# System.net
KiCad netlist of a schematic drawn in Altium Designer
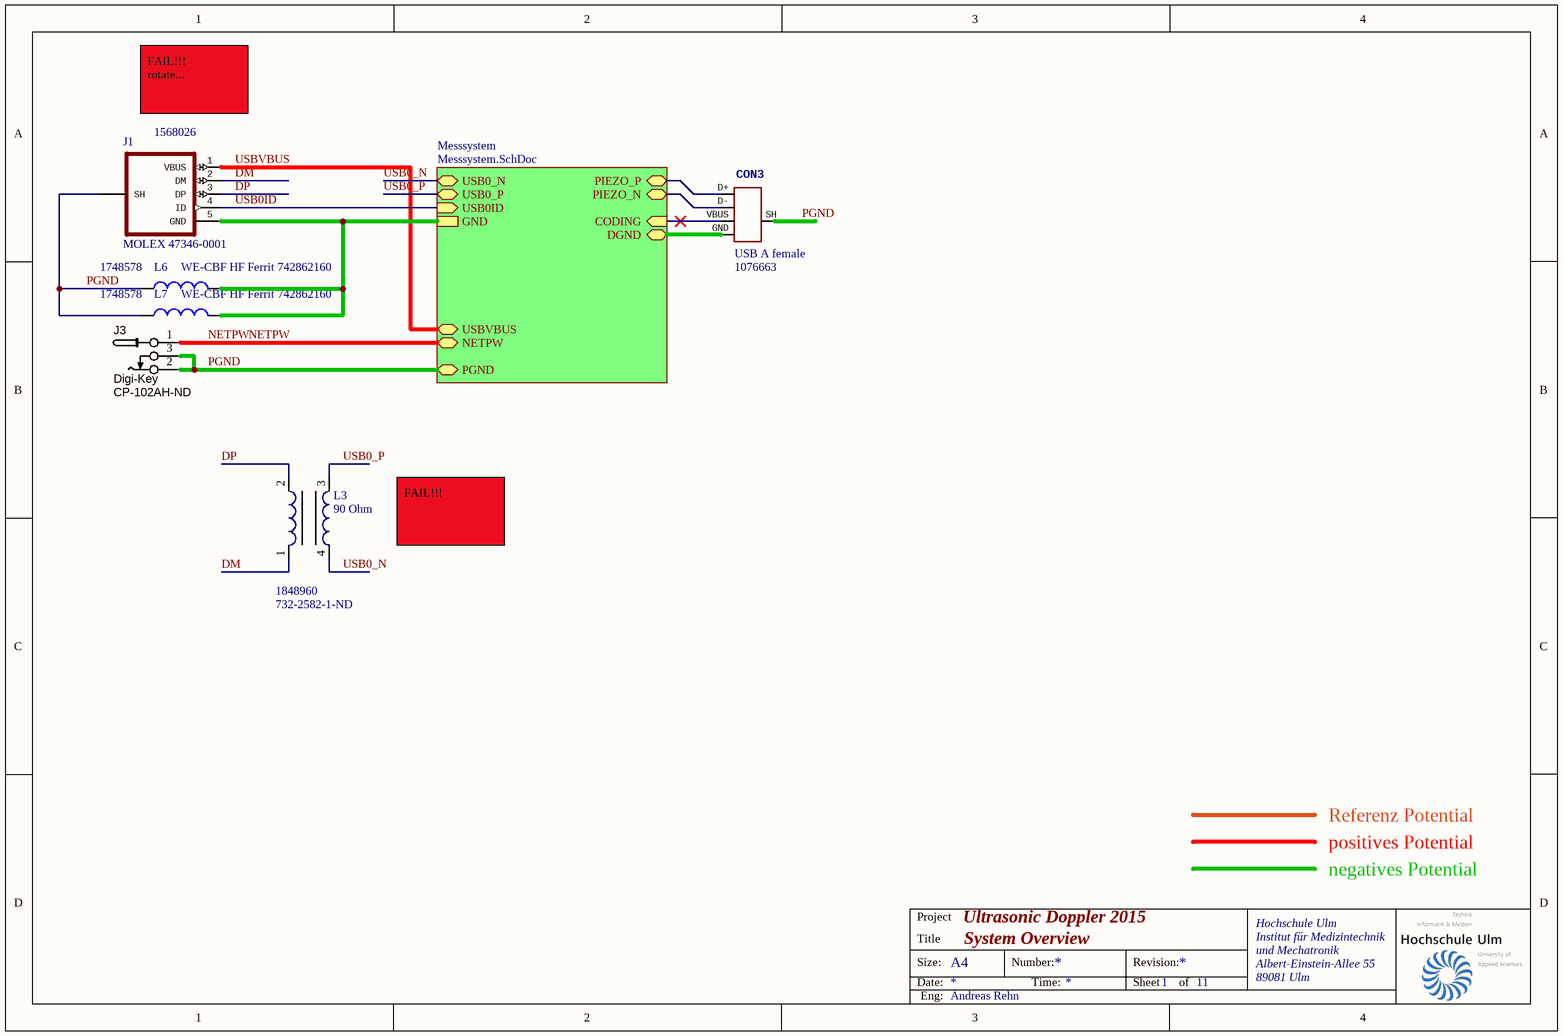
[diagram p0: System.SchDoc]

(export (version "E")
  (design (tool "Eeschema 10.0.6"))
  (components
    (comp (ref "CON3")
      (value "USB A female")
      (footprint "USB A female")
      (fields (field (name "SUPPLIER PART NUMBER 1") "1076663"))
      (libsource (lib "USD Parts") (part "USB-MB-S"))
    )
    (comp (ref "J1")
      (value "MOLEX 47346-0001")
      (footprint "USB Micro")
      (description "MICRO USB 2.0 BUCHSE, TYP B, SMD")
      (fields (field (name "SUPPLIER PART NUMBER 1") "1568026"))
      (libsource (lib "USD Parts") (part "USB"))
    )
    (comp (ref "J3")
      (value "CONN_PWR_JACK_2.1x5.5mm")
      (footprint "CONN_PWR_JACK_2.1x5.5mm")
      (description "Power Connector, THT, 2.1mm ID, 5.5mm OD")
      (fields (field (name "SUPPLIER 1") "Digi-Key") (field (name "SUPPLIER PART NUMBER 1") "CP-102AH-ND"))
      (libsource (lib "USD Parts") (part "CONN_PWR_JACK_2.1x5.5mm"))
    )
    (comp (ref "L3")
      (value "90 Ohm")
      (footprint "WE-CNSW, 0603")
      (description "SMD Common Mode Noise Suppressor WE-CNSW,  Z= 90 Ohm")
      (fields
        (field (name "PARTNO") "744230900")
        (field (name "MANUFACTURER") "Würth Elektronik eiSos GmbH")
        (field (name "SUPPLIER PART NUMBER 1") "1848960")
        (field (name "SUPPLIER PART NUMBER 2") "732-2582-1-ND")
        (field (name "CREATED BY") "Christin Zierenner")
      )
      (libsource (lib "WE-CNSW") (part "WE-CNSW 0603, 744230900"))
    )
    (comp (ref "L6")
      (value "WE-CBF HF Ferrit 742862160")
      (footprint "0603[1508]")
      (description "Ferrit")
      (fields (field (name "SUPPLIER PART NUMBER 1") "1748578") (field (name "PUBLISHER") "Altium Limited"))
      (libsource (lib "Components") (part "Inductor"))
    )
    (comp (ref "L7")
      (value "WE-CBF HF Ferrit 742862160")
      (footprint "0603[1508]")
      (description "Ferrit")
      (fields (field (name "SUPPLIER PART NUMBER 1") "1748578") (field (name "PUBLISHER") "Altium Limited"))
      (libsource (lib "Components") (part "Inductor"))
    )
  )
  (nets
    (net (code "1") (name "/CODING") (class "Default")
      (node (ref "CON3") (pin "VBUS") (pinfunction "VBUS_VBUS") (pintype "power_in"))
    )
    (net (code "2") (name "/DGND") (class "Default")
      (node (ref "CON3") (pin "GND") (pinfunction "GND_GND") (pintype "passive"))
    )
    (net (code "3") (name "/DM") (class "Default")
      (node (ref "J1") (pin "2") (pinfunction "DM_2") (pintype "bidirectional"))
      (node (ref "L3") (pin "1") (pinfunction "1_1") (pintype "passive"))
    )
    (net (code "4") (name "/DP") (class "Default")
      (node (ref "J1") (pin "3") (pinfunction "DP_3") (pintype "bidirectional"))
      (node (ref "L3") (pin "2") (pinfunction "2_2") (pintype "passive"))
    )
    (net (code "5") (name "/GND") (class "Default")
      (node (ref "J1") (pin "5") (pinfunction "GND_5") (pintype "passive"))
      (node (ref "L6") (pin "2") (pinfunction "2_2") (pintype "passive"))
      (node (ref "L7") (pin "2") (pinfunction "2_2") (pintype "passive"))
    )
    (net (code "6") (name "/NETPW") (class "Default")
      (node (ref "J3") (pin "1") (pinfunction "1_1") (pintype "passive"))
    )
    (net (code "7") (name "/PGND") (class "Default")
      (node (ref "CON3") (pin "SH") (pinfunction "SH_SH") (pintype "passive"))
      (node (ref "J1") (pin "SH") (pinfunction "SH_SH") (pintype "passive"))
      (node (ref "J3") (pin "2") (pinfunction "2_2") (pintype "passive"))
      (node (ref "J3") (pin "3") (pinfunction "3_3") (pintype "passive"))
      (node (ref "L6") (pin "1") (pinfunction "1_1") (pintype "passive"))
      (node (ref "L7") (pin "1") (pinfunction "1_1") (pintype "passive"))
    )
    (net (code "8") (name "/PIEZO_N") (class "Default")
      (node (ref "CON3") (pin "D-") (pinfunction "D-_D-") (pintype "passive"))
    )
    (net (code "9") (name "/PIEZO_P") (class "Default")
      (node (ref "CON3") (pin "D+") (pinfunction "D+_D+") (pintype "passive"))
    )
    (net (code "10") (name "/USB0ID") (class "Default")
      (node (ref "J1") (pin "4") (pinfunction "ID_4") (pintype "output"))
    )
    (net (code "11") (name "/USB0_N") (class "Default")
      (node (ref "L3") (pin "4") (pinfunction "4_4") (pintype "passive"))
    )
    (net (code "12") (name "/USB0_P") (class "Default")
      (node (ref "L3") (pin "3") (pinfunction "3_3") (pintype "passive"))
    )
    (net (code "13") (name "/USBVBUS") (class "Default")
      (node (ref "J1") (pin "1") (pinfunction "VBUS_1") (pintype "bidirectional"))
    )
  )
)
